# power_supply.net
KiCad netlist of a schematic drawn in Altium Designer
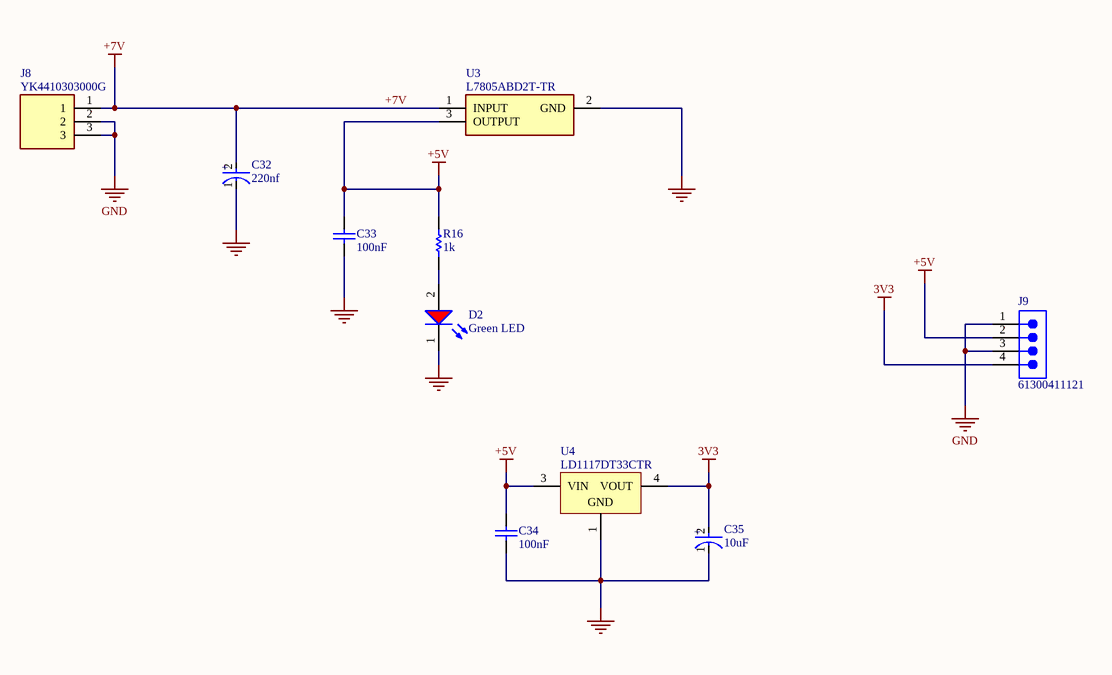
[diagram p0:  power_supply.SchDoc]

(export (version "E")
  (design (tool "Eeschema 10.0.6"))
  (components
    (comp (ref "C32")
      (value "220nf")
      (footprint "FP-RAD-TH-D_8_0_5-L_15_1-MFG")
      (description "Aluminum Electrolytic Capacitors (Radial Lead Type) 120uF ±20% 50V")
      (fields (field (name "TOLERANCE") "20%"))
      (libsource (lib "Altium Content Vault") (part "a00bbbee19879c290e62620ae7e47b1"))
    )
    (comp (ref "C33")
      (value "100nF")
      (footprint "CAPC2013X140X45NL15T25")
      (fields (field (name "MANUFACTURER") "Murata") (field (name "PART NUMBER") "GCM21BR71H104KA37K"))
      (libsource (lib "Altium Content Vault") (part "CAP"))
    )
    (comp (ref "C34")
      (value "100nF")
      (footprint "CAPC2013X140X45NL15T25")
      (fields (field (name "MANUFACTURER") "Murata") (field (name "PART NUMBER") "GCM21BR71H104KA37K"))
      (libsource (lib "Altium Content Vault") (part "CAP"))
    )
    (comp (ref "C35")
      (value "10uF")
      (footprint "FP-TAJP-MFG")
      (description "10uF 10V  ±20% 6Ω 0805  SMD Tantalum Capacitor")
      (fields (field (name "TOLERANCE") "20%") (field (name "VOLTAGE") "10V"))
      (libsource (lib "Altium Content Vault") (part "a00bbbee19879c290e62620ae7e47b1"))
    )
    (comp (ref "D2")
      (value "Green LED")
      (footprint "WL-SMCW_0603_150060xx75000")
      (description "LED Low-Power Uni-Color Green 630nm 2V 2-Pin Chip 0603(1608Metric) T/R")
      (libsource (lib "Altium Content Vault") (part "LED_Red_2A-1K"))
    )
    (comp (ref "J8")
      (value "YK4410303000G")
      (footprint "SamacSys:YK4410303000G")
      (description "Connector")
      (fields (field (name "MOUSER PART NUMBER") "649-YK44103030J0G"))
      (libsource (lib "*") (part "YK4410303000G"))
    )
    (comp (ref "J9")
      (value "61300411121")
      (footprint "61300411121")
      (libsource (lib "Altium Content Vault") (part "Header_Male_1R_04P"))
    )
    (comp (ref "R16")
      (value "1k")
      (footprint "RESC2013X60X35ML10T20")
      (description "Chip Resistor, 1 KOhm, +/- 1%, 125 mW, -55 to 155 degC, 0805 (2012 Metric), RoHS, Tape and Reel")
      (fields (field (name "TOLERANCE") "1%") (field (name "MANUFACTURER") "Yageo"))
      (libsource (lib "Altium Content Vault") (part "RES-2"))
    )
    (comp (ref "U3")
      (value "L7805ABD2T-TR")
      (footprint "SamacSys:L7805ABD2TTR")
      (description "Integrated Circuit")
      (fields (field (name "MOUSER PART NUMBER") "511-L7805ABD2T-TR"))
      (libsource (lib "*") (part "L7805ABD2T-TR"))
    )
    (comp (ref "U4")
      (value "LD1117DT33CTR")
      (footprint "TO-252_N")
      (description "Fixed Low Drop Positive Voltage Regulator, 3.3V, 3-Pin DPAK, Tape and Reel")
      (libsource (lib "Altium Content Vault") (part "PM-REG-LD1117-SOT3"))
    )
  )
  (nets
    (net (code "1") (name "+5V") (class "Default")
      (node (ref "C33") (pin "2") (pinfunction "2_2") (pintype "passive"))
      (node (ref "C34") (pin "2") (pinfunction "2_2") (pintype "passive"))
      (node (ref "J9") (pin "2") (pinfunction "2_2") (pintype "passive"))
      (node (ref "R16") (pin "2") (pinfunction "2_2") (pintype "passive"))
      (node (ref "U3") (pin "3") (pinfunction "OUTPUT_3") (pintype "passive"))
      (node (ref "U4") (pin "3") (pinfunction "VIN_3") (pintype "passive"))
    )
    (net (code "2") (name "+7V") (class "Default")
      (node (ref "C32") (pin "2") (pinfunction "A_2") (pintype "passive"))
      (node (ref "J8") (pin "1") (pinfunction "1_1") (pintype "passive"))
      (node (ref "U3") (pin "1") (pinfunction "INPUT_1") (pintype "passive"))
    )
    (net (code "3") (name "3V3") (class "Default")
      (node (ref "C35") (pin "2") (pinfunction "A_2") (pintype "passive"))
      (node (ref "J9") (pin "4") (pinfunction "4_4") (pintype "passive"))
      (node (ref "U4") (pin "4") (pinfunction "VOUT_4") (pintype "power_in"))
    )
    (net (code "4") (name "GND") (class "Default")
      (node (ref "C32") (pin "1") (pinfunction "C_1") (pintype "passive"))
      (node (ref "C33") (pin "1") (pinfunction "1_1") (pintype "passive"))
      (node (ref "C34") (pin "1") (pinfunction "1_1") (pintype "passive"))
      (node (ref "C35") (pin "1") (pinfunction "C_1") (pintype "passive"))
      (node (ref "D2") (pin "1") (pinfunction "K_1") (pintype "passive"))
      (node (ref "J8") (pin "2") (pinfunction "2_2") (pintype "passive"))
      (node (ref "J8") (pin "3") (pinfunction "3_3") (pintype "passive"))
      (node (ref "J9") (pin "1") (pinfunction "1_1") (pintype "passive"))
      (node (ref "J9") (pin "3") (pinfunction "3_3") (pintype "passive"))
      (node (ref "U3") (pin "2") (pinfunction "GND_2") (pintype "passive"))
      (node (ref "U4") (pin "1") (pinfunction "GND_1") (pintype "power_in"))
    )
    (net (code "5") (name "Net-(D2-A)") (class "Default")
      (node (ref "D2") (pin "2") (pinfunction "A_2") (pintype "passive"))
      (node (ref "R16") (pin "1") (pinfunction "1_1") (pintype "passive"))
    )
  )
)
